# HALL_SENSOR_FILTER.net
KiCad netlist of a schematic drawn in Altium Designer
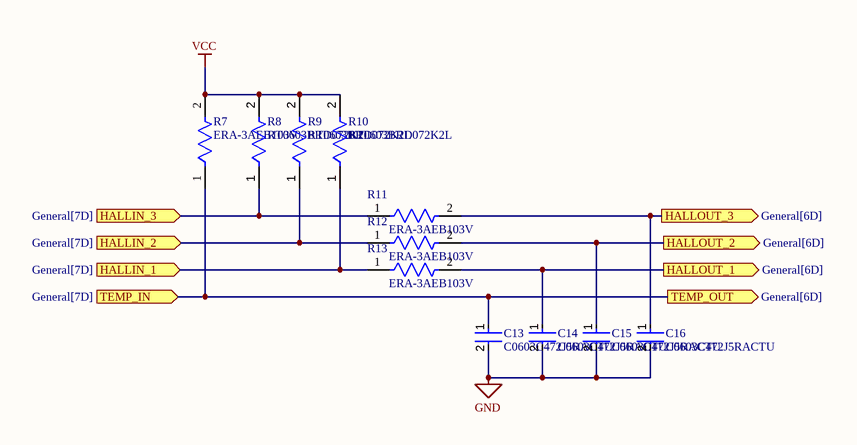
[diagram p0: HALL_SENSOR_FILTER.SchDoc]

(export (version "E")
  (design (tool "Eeschema 10.0.6"))
  (components
    (comp (ref "C13")
      (value "C0603C472J5RACTU")
      (footprint "FP-C0603C-CF-MFG")
      (description "C0603C 4.7nF Ceramic Multilayer Capacitor; 50 VDC; +125degC; X7R Dielec; +/-5%")
      (fields
        (field (name "TOLERANCE") "0.05")
        (field (name "OCTOPART") "https://octopart.com/c0603c472j5ractu-kemet-107195")
      )
      (libsource (lib "Altium Content Vault") (part "b4654b650e69147ec39a6b967a45e02"))
    )
    (comp (ref "C14")
      (value "C0603C472J5RACTU")
      (footprint "FP-C0603C-CF-MFG")
      (description "C0603C 4.7nF Ceramic Multilayer Capacitor; 50 VDC; +125degC; X7R Dielec; +/-5%")
      (fields
        (field (name "TOLERANCE") "0.05")
        (field (name "OCTOPART") "https://octopart.com/c0603c472j5ractu-kemet-107195")
      )
      (libsource (lib "Altium Content Vault") (part "b4654b650e69147ec39a6b967a45e02"))
    )
    (comp (ref "C15")
      (value "C0603C472J5RACTU")
      (footprint "FP-C0603C-CF-MFG")
      (description "C0603C 4.7nF Ceramic Multilayer Capacitor; 50 VDC; +125degC; X7R Dielec; +/-5%")
      (fields
        (field (name "TOLERANCE") "0.05")
        (field (name "OCTOPART") "https://octopart.com/c0603c472j5ractu-kemet-107195")
      )
      (libsource (lib "Altium Content Vault") (part "b4654b650e69147ec39a6b967a45e02"))
    )
    (comp (ref "C16")
      (value "C0603C472J5RACTU")
      (footprint "FP-C0603C-CF-MFG")
      (description "C0603C 4.7nF Ceramic Multilayer Capacitor; 50 VDC; +125degC; X7R Dielec; +/-5%")
      (fields
        (field (name "TOLERANCE") "0.05")
        (field (name "OCTOPART") "https://octopart.com/c0603c472j5ractu-kemet-107195")
      )
      (libsource (lib "Altium Content Vault") (part "b4654b650e69147ec39a6b967a45e02"))
    )
    (comp (ref "R7")
      (value "ERA-3AEB103V")
      (footprint "FP-ERA3A-IPC_C")
      (description "RES SMD 10K OHM 0.1% 1/10W 0603")
      (fields (field (name "TOLERANCE") "0.1%"))
      (libsource (lib "Altium Content Vault") (part "4e5f8b3dd332802e91518312df5df73"))
    )
    (comp (ref "R8")
      (value "RT0603BRD072K2L")
      (footprint "FP-RT0603-MFG")
      (description "RES 2.20K OHM 1/10W .1% SMD 0603")
      (fields
        (field (name "OCTOPART") "https://octopart.com/rt0603brd072k2l-yageo-1186019")
        (field (name "MANUFACTURER") "Yageo")
      )
      (libsource (lib "Altium Content Vault") (part "1029c3af85768c4190bb7ad29bc67b5"))
    )
    (comp (ref "R9")
      (value "RT0603BRD072K2L")
      (footprint "FP-RT0603-MFG")
      (description "RES 2.20K OHM 1/10W .1% SMD 0603")
      (fields
        (field (name "OCTOPART") "https://octopart.com/rt0603brd072k2l-yageo-1186019")
        (field (name "MANUFACTURER") "Yageo")
      )
      (libsource (lib "Altium Content Vault") (part "1029c3af85768c4190bb7ad29bc67b5"))
    )
    (comp (ref "R10")
      (value "RT0603BRD072K2L")
      (footprint "FP-RT0603-MFG")
      (description "RES 2.20K OHM 1/10W .1% SMD 0603")
      (fields
        (field (name "OCTOPART") "https://octopart.com/rt0603brd072k2l-yageo-1186019")
        (field (name "MANUFACTURER") "Yageo")
      )
      (libsource (lib "Altium Content Vault") (part "1029c3af85768c4190bb7ad29bc67b5"))
    )
    (comp (ref "R11")
      (value "ERA-3AEB103V")
      (footprint "FP-ERA3A-IPC_C")
      (description "RES SMD 10K OHM 0.1% 1/10W 0603")
      (fields (field (name "TOLERANCE") "0.1%"))
      (libsource (lib "Altium Content Vault") (part "4e5f8b3dd332802e91518312df5df73"))
    )
    (comp (ref "R12")
      (value "ERA-3AEB103V")
      (footprint "FP-ERA3A-IPC_C")
      (description "RES SMD 10K OHM 0.1% 1/10W 0603")
      (fields (field (name "TOLERANCE") "0.1%"))
      (libsource (lib "Altium Content Vault") (part "4e5f8b3dd332802e91518312df5df73"))
    )
    (comp (ref "R13")
      (value "ERA-3AEB103V")
      (footprint "FP-ERA3A-IPC_C")
      (description "RES SMD 10K OHM 0.1% 1/10W 0603")
      (fields (field (name "TOLERANCE") "0.1%"))
      (libsource (lib "Altium Content Vault") (part "4e5f8b3dd332802e91518312df5df73"))
    )
  )
  (nets
    (net (code "1") (name "/HALLIN_1") (class "Default")
      (node (ref "R10") (pin "1") (pinfunction "1_1") (pintype "passive"))
      (node (ref "R13") (pin "1") (pinfunction "1_1") (pintype "passive"))
    )
    (net (code "2") (name "/HALLIN_2") (class "Default")
      (node (ref "R12") (pin "1") (pinfunction "1_1") (pintype "passive"))
      (node (ref "R9") (pin "1") (pinfunction "1_1") (pintype "passive"))
    )
    (net (code "3") (name "/HALLIN_3") (class "Default")
      (node (ref "R11") (pin "1") (pinfunction "1_1") (pintype "passive"))
      (node (ref "R8") (pin "1") (pinfunction "1_1") (pintype "passive"))
    )
    (net (code "4") (name "/HALLOUT_1") (class "Default")
      (node (ref "C14") (pin "1") (pinfunction "1_1") (pintype "passive"))
      (node (ref "R13") (pin "2") (pinfunction "2_2") (pintype "passive"))
    )
    (net (code "5") (name "/HALLOUT_2") (class "Default")
      (node (ref "C15") (pin "1") (pinfunction "1_1") (pintype "passive"))
      (node (ref "R12") (pin "2") (pinfunction "2_2") (pintype "passive"))
    )
    (net (code "6") (name "/HALLOUT_3") (class "Default")
      (node (ref "C16") (pin "1") (pinfunction "1_1") (pintype "passive"))
      (node (ref "R11") (pin "2") (pinfunction "2_2") (pintype "passive"))
    )
    (net (code "7") (name "/TEMP_IN") (class "Default")
      (node (ref "C13") (pin "1") (pinfunction "1_1") (pintype "passive"))
      (node (ref "R7") (pin "1") (pinfunction "1_1") (pintype "passive"))
    )
    (net (code "8") (name "GND") (class "Default")
      (node (ref "C13") (pin "2") (pinfunction "2_2") (pintype "passive"))
      (node (ref "C14") (pin "2") (pinfunction "2_2") (pintype "passive"))
      (node (ref "C15") (pin "2") (pinfunction "2_2") (pintype "passive"))
      (node (ref "C16") (pin "2") (pinfunction "2_2") (pintype "passive"))
    )
    (net (code "9") (name "VCC") (class "Default")
      (node (ref "R10") (pin "2") (pinfunction "2_2") (pintype "passive"))
      (node (ref "R7") (pin "2") (pinfunction "2_2") (pintype "passive"))
      (node (ref "R8") (pin "2") (pinfunction "2_2") (pintype "passive"))
      (node (ref "R9") (pin "2") (pinfunction "2_2") (pintype "passive"))
    )
  )
)
